# ONOFRE_ESTORES_COVERS_R3_0.net
KiCad netlist of a schematic drawn in EAGLE
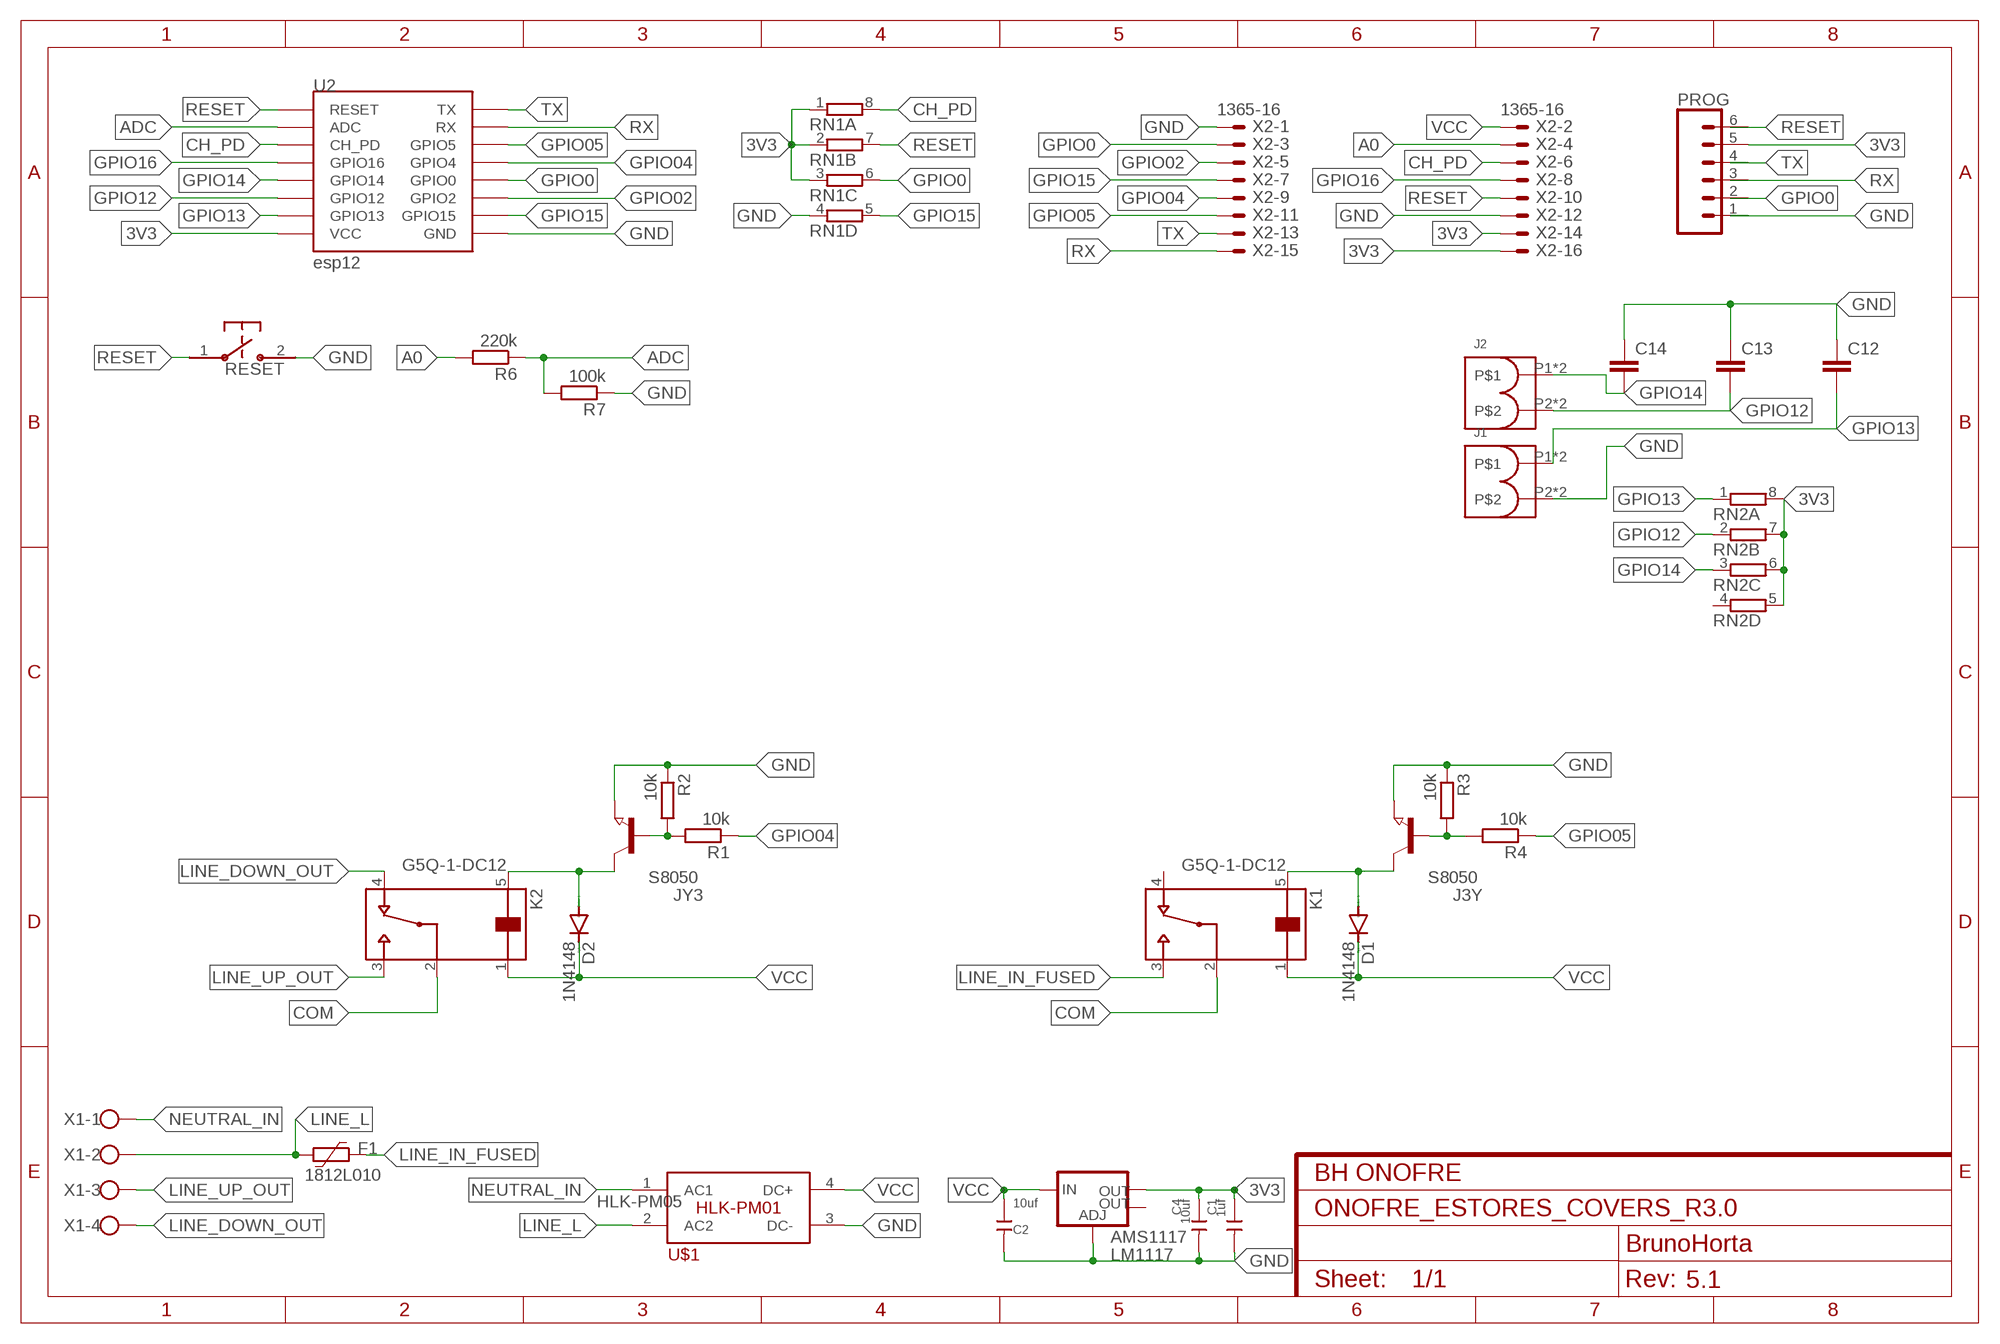
[diagram p0: schematic, sheet 1]

(export (version "E")
  (design (tool "Eeschema 10.0.6"))
  (components
    (comp (ref "AMS1117")
      (value "LM1117")
      (footprint "eagle-import:SOT223")
      (libsource (lib "eagle-import") (part "V_REG_LM1117SOT223"))
    )
    (comp (ref "C1")
      (value "1uf")
      (footprint "eagle-import:C1206")
      (fields (field (name "MPN") "CC1206KKX7RCBB102"))
      (libsource (lib "eagle-import") (part "CERAMIC-1NF-1KV-10%-X7R?(1206)"))
    )
    (comp (ref "C2")
      (value "10uf")
      (footprint "eagle-import:C1206")
      (fields (field (name "MPN") "CC1206KKX7RCBB102"))
      (libsource (lib "eagle-import") (part "CERAMIC-1NF-1KV-10%-X7R?(1206)"))
    )
    (comp (ref "C4")
      (value "10uf")
      (footprint "eagle-import:C1206")
      (fields (field (name "MPN") "CC1206KKX7RCBB102"))
      (libsource (lib "eagle-import") (part "CERAMIC-1NF-1KV-10%-X7R?(1206)"))
    )
    (comp (ref "C12")
      (value "C-EUC0805")
      (footprint "eagle-import:C0805")
      (libsource (lib "eagle-import") (part "C-EUC0805"))
    )
    (comp (ref "C13")
      (value "C-EUC0805")
      (footprint "eagle-import:C0805")
      (libsource (lib "eagle-import") (part "C-EUC0805"))
    )
    (comp (ref "C14")
      (value "C-EUC0805")
      (footprint "eagle-import:C0805")
      (libsource (lib "eagle-import") (part "C-EUC0805"))
    )
    (comp (ref "D1")
      (value "1N4148")
      (footprint "eagle-import:SOD80C")
      (libsource (lib "eagle-import") (part "DIODE-SOD80C"))
    )
    (comp (ref "D2")
      (value "1N4148")
      (footprint "eagle-import:SOD80C")
      (libsource (lib "eagle-import") (part "DIODE-SOD80C"))
    )
    (comp (ref "F1")
      (value "1812L010")
      (footprint "eagle-import:1812L")
      (fields (field (name "MF") "Littelfuse"))
      (libsource (lib "eagle-import") (part "?1812L010"))
    )
    (comp (ref "J1")
      (value "46.142.1001")
      (footprint "eagle-import:P_46.142.1001")
      (libsource (lib "eagle-import") (part "46.142.1001"))
    )
    (comp (ref "J2")
      (value "46.142.1001")
      (footprint "eagle-import:P_46.142.1001")
      (libsource (lib "eagle-import") (part "46.142.1001"))
    )
    (comp (ref "J3Y")
      (value "S8050")
      (footprint "eagle-import:SOT23")
      (libsource (lib "eagle-import") (part "NPN-TRANSISTOR_SOT23"))
    )
    (comp (ref "JY3")
      (value "S8050")
      (footprint "eagle-import:SOT23")
      (libsource (lib "eagle-import") (part "NPN-TRANSISTOR_SOT23"))
    )
    (comp (ref "K1")
      (value "G5Q-1-DC12")
      (footprint "eagle-import:RELAY_G5Q-1-DC12")
      (fields (field (name "MF") "Omron"))
      (libsource (lib "eagle-import") (part "G5Q-1-DC12"))
    )
    (comp (ref "K2")
      (value "G5Q-1-DC12")
      (footprint "eagle-import:RELAY_G5Q-1-DC12")
      (fields (field (name "MF") "Omron"))
      (libsource (lib "eagle-import") (part "G5Q-1-DC12"))
    )
    (comp (ref "PROG")
      (value "CONN_06NO_SILK_NO_POP")
      (footprint "eagle-import:1X06_NO_SILK")
      (libsource (lib "eagle-import") (part "CONN_06NO_SILK_NO_POP"))
    )
    (comp (ref "R1")
      (value "10k")
      (footprint "eagle-import:R0603")
      (libsource (lib "eagle-import") (part "R-EU_R0603"))
    )
    (comp (ref "R2")
      (value "10k")
      (footprint "eagle-import:R0603")
      (libsource (lib "eagle-import") (part "R-EU_R0603"))
    )
    (comp (ref "R3")
      (value "10k")
      (footprint "eagle-import:R0603")
      (libsource (lib "eagle-import") (part "R-EU_R0603"))
    )
    (comp (ref "R4")
      (value "10k")
      (footprint "eagle-import:R0603")
      (libsource (lib "eagle-import") (part "R-EU_R0603"))
    )
    (comp (ref "R6")
      (value "220k")
      (footprint "eagle-import:R0603")
      (libsource (lib "eagle-import") (part "R-EU_R0603"))
    )
    (comp (ref "R7")
      (value "100k")
      (footprint "eagle-import:R0603")
      (libsource (lib "eagle-import") (part "R-EU_R0603"))
    )
    (comp (ref "RESET")
      (value "B3U-1000P-2P-SMD")
      (footprint "eagle-import:B3U-1000P")
      (fields (field (name "MANUFACTURER") "Omron") (field (name "MPN") "B3U-1000P"))
      (libsource (lib "eagle-import") (part "B3U-1000P"))
    )
    (comp (ref "RN1")
      (value "4R-N0603-ARV")
      (footprint "eagle-import:0603-ARV")
      (libsource (lib "eagle-import") (part "4R-N0603-ARV"))
    )
    (comp (ref "RN2")
      (value "4R-N0603-ARV")
      (footprint "eagle-import:0603-ARV")
      (libsource (lib "eagle-import") (part "4R-N0603-ARV"))
    )
    (comp (ref "U$1")
      (value "HLK-PM01")
      (footprint "eagle-import:HLK-PM01")
      (fields (field (name "MF") "Hi-link") (field (name "MP") "hlk-pm01"))
      (libsource (lib "eagle-import") (part "HLK-PM01"))
    )
    (comp (ref "U2")
      (value "esp12")
      (footprint "eagle-import:ESP12-SMD")
      (libsource (lib "eagle-import") (part "ESP12SMD"))
    )
    (comp (ref "X1")
      (value "W237-4")
      (footprint "eagle-import:W237-4")
      (libsource (lib "eagle-import") (part "W237-4"))
    )
    (comp (ref "X2")
      (value "1365-16")
      (footprint "eagle-import:1365-16")
      (fields (field (name "SPICEPREFIX") "X"))
      (libsource (lib "eagle-import") (part "1365-16"))
    )
  )
  (nets
    (net (code "1") (name "3V3") (class "Default")
      (node (ref "AMS1117") (pin "2") (pinfunction "OUT_2") (pintype "output"))
      (node (ref "C1") (pin "1") (pinfunction "1_1") (pintype "passive"))
      (node (ref "C4") (pin "1") (pinfunction "1_1") (pintype "passive"))
      (node (ref "PROG") (pin "5") (pinfunction "5_5") (pintype "passive"))
      (node (ref "RN1") (pin "1") (pinfunction "1_1") (pintype "passive"))
      (node (ref "RN1") (pin "2") (pinfunction "1_2") (pintype "passive"))
      (node (ref "RN1") (pin "3") (pinfunction "1_3") (pintype "passive"))
      (node (ref "RN2") (pin "5") (pinfunction "2_5") (pintype "passive"))
      (node (ref "RN2") (pin "6") (pinfunction "2_6") (pintype "passive"))
      (node (ref "RN2") (pin "7") (pinfunction "2_7") (pintype "passive"))
      (node (ref "RN2") (pin "8") (pinfunction "2_8") (pintype "passive"))
      (node (ref "U2") (pin "VCC") (pinfunction "VCC_VCC") (pintype "bidirectional"))
      (node (ref "X2") (pin "14") (pinfunction "S_14") (pintype "passive"))
      (node (ref "X2") (pin "16") (pinfunction "S_16") (pintype "passive"))
    )
    (net (code "2") (name "A0") (class "Default")
      (node (ref "R6") (pin "2") (pinfunction "2_2") (pintype "passive"))
      (node (ref "X2") (pin "4") (pinfunction "S_4") (pintype "passive"))
    )
    (net (code "3") (name "ADC") (class "Default")
      (node (ref "R6") (pin "1") (pinfunction "1_1") (pintype "passive"))
      (node (ref "R7") (pin "2") (pinfunction "2_2") (pintype "passive"))
      (node (ref "U2") (pin "ADC") (pinfunction "ADC_ADC") (pintype "bidirectional"))
    )
    (net (code "4") (name "CH_PD") (class "Default")
      (node (ref "RN1") (pin "8") (pinfunction "2_8") (pintype "passive"))
      (node (ref "U2") (pin "CH_PD") (pinfunction "CH_PD_CH_PD") (pintype "bidirectional"))
      (node (ref "X2") (pin "6") (pinfunction "S_6") (pintype "passive"))
    )
    (net (code "5") (name "COM") (class "Default")
      (node (ref "K1") (pin "2") (pinfunction "2_2") (pintype "passive"))
      (node (ref "K2") (pin "2") (pinfunction "2_2") (pintype "passive"))
    )
    (net (code "6") (name "GND") (class "Default")
      (node (ref "AMS1117") (pin "1") (pinfunction "ADJ_1") (pintype "input"))
      (node (ref "C1") (pin "2") (pinfunction "2_2") (pintype "passive"))
      (node (ref "C12") (pin "1") (pinfunction "1_1") (pintype "passive"))
      (node (ref "C13") (pin "1") (pinfunction "1_1") (pintype "passive"))
      (node (ref "C14") (pin "1") (pinfunction "1_1") (pintype "passive"))
      (node (ref "C2") (pin "2") (pinfunction "2_2") (pintype "passive"))
      (node (ref "C4") (pin "2") (pinfunction "2_2") (pintype "passive"))
      (node (ref "J1") (pin "P2") (pinfunction "P$2_P2") (pintype "bidirectional"))
      (node (ref "J1") (pin "P2.1") (pinfunction "P$2_P2.1") (pintype "bidirectional"))
      (node (ref "J3Y") (pin "2") (pinfunction "E_2") (pintype "passive"))
      (node (ref "JY3") (pin "2") (pinfunction "E_2") (pintype "passive"))
      (node (ref "PROG") (pin "1") (pinfunction "1_1") (pintype "passive"))
      (node (ref "R2") (pin "1") (pinfunction "1_1") (pintype "passive"))
      (node (ref "R3") (pin "1") (pinfunction "1_1") (pintype "passive"))
      (node (ref "R7") (pin "1") (pinfunction "1_1") (pintype "passive"))
      (node (ref "RESET") (pin "2") (pinfunction "P$2_2") (pintype "passive"))
      (node (ref "RN1") (pin "4") (pinfunction "1_4") (pintype "passive"))
      (node (ref "U$1") (pin "3") (pinfunction "DC-_3") (pintype "power_in"))
      (node (ref "U2") (pin "GND") (pinfunction "GND_GND") (pintype "bidirectional"))
      (node (ref "X2") (pin "1") (pinfunction "S_1") (pintype "passive"))
      (node (ref "X2") (pin "12") (pinfunction "S_12") (pintype "passive"))
    )
    (net (code "7") (name "GPIO0") (class "Default")
      (node (ref "PROG") (pin "2") (pinfunction "2_2") (pintype "passive"))
      (node (ref "RN1") (pin "6") (pinfunction "2_6") (pintype "passive"))
      (node (ref "U2") (pin "GPIO0") (pinfunction "GPIO0_GPIO0") (pintype "bidirectional"))
      (node (ref "X2") (pin "3") (pinfunction "S_3") (pintype "passive"))
    )
    (net (code "8") (name "GPIO02") (class "Default")
      (node (ref "U2") (pin "GPIO2") (pinfunction "GPIO2_GPIO2") (pintype "bidirectional"))
      (node (ref "X2") (pin "5") (pinfunction "S_5") (pintype "passive"))
    )
    (net (code "9") (name "GPIO04") (class "Default")
      (node (ref "R1") (pin "1") (pinfunction "1_1") (pintype "passive"))
      (node (ref "U2") (pin "GPIO4") (pinfunction "GPIO4_GPIO4") (pintype "bidirectional"))
      (node (ref "X2") (pin "9") (pinfunction "S_9") (pintype "passive"))
    )
    (net (code "10") (name "GPIO05") (class "Default")
      (node (ref "R4") (pin "1") (pinfunction "1_1") (pintype "passive"))
      (node (ref "U2") (pin "GPIO5") (pinfunction "GPIO5_GPIO5") (pintype "bidirectional"))
      (node (ref "X2") (pin "11") (pinfunction "S_11") (pintype "passive"))
    )
    (net (code "11") (name "GPIO12") (class "Default")
      (node (ref "C13") (pin "2") (pinfunction "2_2") (pintype "passive"))
      (node (ref "J2") (pin "P2") (pinfunction "P$2_P2") (pintype "bidirectional"))
      (node (ref "J2") (pin "P2.1") (pinfunction "P$2_P2.1") (pintype "bidirectional"))
      (node (ref "RN2") (pin "2") (pinfunction "1_2") (pintype "passive"))
      (node (ref "U2") (pin "GPIO12") (pinfunction "GPIO12_GPIO12") (pintype "bidirectional"))
    )
    (net (code "12") (name "GPIO13") (class "Default")
      (node (ref "C12") (pin "2") (pinfunction "2_2") (pintype "passive"))
      (node (ref "J1") (pin "P1") (pinfunction "P$1_P1") (pintype "bidirectional"))
      (node (ref "J1") (pin "P1.1") (pinfunction "P$1_P1.1") (pintype "bidirectional"))
      (node (ref "RN2") (pin "1") (pinfunction "1_1") (pintype "passive"))
      (node (ref "U2") (pin "GPIO13") (pinfunction "GPIO13_GPIO13") (pintype "bidirectional"))
    )
    (net (code "13") (name "GPIO14") (class "Default")
      (node (ref "C14") (pin "2") (pinfunction "2_2") (pintype "passive"))
      (node (ref "J2") (pin "P1") (pinfunction "P$1_P1") (pintype "bidirectional"))
      (node (ref "J2") (pin "P1.1") (pinfunction "P$1_P1.1") (pintype "bidirectional"))
      (node (ref "RN2") (pin "3") (pinfunction "1_3") (pintype "passive"))
      (node (ref "U2") (pin "GPIO14") (pinfunction "GPIO14_GPIO14") (pintype "bidirectional"))
    )
    (net (code "14") (name "GPIO15") (class "Default")
      (node (ref "RN1") (pin "5") (pinfunction "2_5") (pintype "passive"))
      (node (ref "U2") (pin "GPIO15") (pinfunction "GPIO15_GPIO15") (pintype "bidirectional"))
      (node (ref "X2") (pin "7") (pinfunction "S_7") (pintype "passive"))
    )
    (net (code "15") (name "GPIO16") (class "Default")
      (node (ref "U2") (pin "GPIO16") (pinfunction "GPIO16_GPIO16") (pintype "bidirectional"))
      (node (ref "X2") (pin "8") (pinfunction "S_8") (pintype "passive"))
    )
    (net (code "16") (name "LINE_DOWN_OUT") (class "Default")
      (node (ref "K2") (pin "4") (pinfunction "4_4") (pintype "passive"))
      (node (ref "X1") (pin "4") (pinfunction "KL_4") (pintype "passive"))
    )
    (net (code "17") (name "LINE_IN_FUSED") (class "Default")
      (node (ref "F1") (pin "1") (pinfunction "1_1") (pintype "passive"))
      (node (ref "K1") (pin "3") (pinfunction "3_3") (pintype "passive"))
    )
    (net (code "18") (name "LINE_L") (class "Default")
      (node (ref "F1") (pin "2") (pinfunction "2_2") (pintype "passive"))
      (node (ref "U$1") (pin "2") (pinfunction "AC2_2") (pintype "power_in"))
      (node (ref "X1") (pin "2") (pinfunction "KL_2") (pintype "passive"))
    )
    (net (code "19") (name "LINE_UP_OUT") (class "Default")
      (node (ref "K2") (pin "3") (pinfunction "3_3") (pintype "passive"))
      (node (ref "X1") (pin "3") (pinfunction "KL_3") (pintype "passive"))
    )
    (net (code "20") (name "NEUTRAL_IN") (class "Default")
      (node (ref "U$1") (pin "1") (pinfunction "AC1_1") (pintype "power_in"))
      (node (ref "X1") (pin "1") (pinfunction "KL_1") (pintype "passive"))
    )
    (net (code "21") (name "Net-(J3Y-B)") (class "Default")
      (node (ref "J3Y") (pin "1") (pinfunction "B_1") (pintype "passive"))
      (node (ref "R3") (pin "2") (pinfunction "2_2") (pintype "passive"))
      (node (ref "R4") (pin "2") (pinfunction "2_2") (pintype "passive"))
    )
    (net (code "22") (name "Net-(J3Y-C)") (class "Default")
      (node (ref "D1") (pin "A") (pinfunction "A_A") (pintype "passive"))
      (node (ref "J3Y") (pin "3") (pinfunction "C_3") (pintype "passive"))
      (node (ref "K1") (pin "5") (pinfunction "5_5") (pintype "passive"))
    )
    (net (code "23") (name "Net-(JY3-B)") (class "Default")
      (node (ref "JY3") (pin "1") (pinfunction "B_1") (pintype "passive"))
      (node (ref "R1") (pin "2") (pinfunction "2_2") (pintype "passive"))
      (node (ref "R2") (pin "2") (pinfunction "2_2") (pintype "passive"))
    )
    (net (code "24") (name "Net-(JY3-C)") (class "Default")
      (node (ref "D2") (pin "A") (pinfunction "A_A") (pintype "passive"))
      (node (ref "JY3") (pin "3") (pinfunction "C_3") (pintype "passive"))
      (node (ref "K2") (pin "5") (pinfunction "5_5") (pintype "passive"))
    )
    (net (code "25") (name "RESET") (class "Default")
      (node (ref "PROG") (pin "6") (pinfunction "6_6") (pintype "passive"))
      (node (ref "RESET") (pin "1") (pinfunction "P$1_1") (pintype "passive"))
      (node (ref "RN1") (pin "7") (pinfunction "2_7") (pintype "passive"))
      (node (ref "U2") (pin "RESET") (pinfunction "RESET_RESET") (pintype "bidirectional"))
      (node (ref "X2") (pin "10") (pinfunction "S_10") (pintype "passive"))
    )
    (net (code "26") (name "RX") (class "Default")
      (node (ref "PROG") (pin "3") (pinfunction "3_3") (pintype "passive"))
      (node (ref "U2") (pin "RXD0") (pinfunction "RX_RXD0") (pintype "bidirectional"))
      (node (ref "X2") (pin "15") (pinfunction "S_15") (pintype "passive"))
    )
    (net (code "27") (name "TX") (class "Default")
      (node (ref "PROG") (pin "4") (pinfunction "4_4") (pintype "passive"))
      (node (ref "U2") (pin "TXD0") (pinfunction "TX_TXD0") (pintype "bidirectional"))
      (node (ref "X2") (pin "13") (pinfunction "S_13") (pintype "passive"))
    )
    (net (code "28") (name "VCC") (class "Default")
      (node (ref "AMS1117") (pin "3") (pinfunction "IN_3") (pintype "input"))
      (node (ref "C2") (pin "1") (pinfunction "1_1") (pintype "passive"))
      (node (ref "D1") (pin "C") (pinfunction "C_C") (pintype "passive"))
      (node (ref "D2") (pin "C") (pinfunction "C_C") (pintype "passive"))
      (node (ref "K1") (pin "1") (pinfunction "1_1") (pintype "passive"))
      (node (ref "K2") (pin "1") (pinfunction "1_1") (pintype "passive"))
      (node (ref "U$1") (pin "4") (pinfunction "DC+_4") (pintype "power_in"))
      (node (ref "X2") (pin "2") (pinfunction "S_2") (pintype "passive"))
    )
    (net (code "29") (name "unconnected-(AMS1117-OUT-Pad4)") (class "Default")
      (node (ref "AMS1117") (pin "4") (pinfunction "OUT_4") (pintype "output"))
    )
    (net (code "30") (name "unconnected-(K1-Pad4)") (class "Default")
      (node (ref "K1") (pin "4") (pinfunction "4_4") (pintype "passive"))
    )
    (net (code "31") (name "unconnected-(RN2D-1-Pad4)") (class "Default")
      (node (ref "RN2") (pin "4") (pinfunction "1_4") (pintype "passive"))
    )
  )
)
